# 9_EXTRAS.net
KiCad netlist of a schematic drawn in Altium Designer
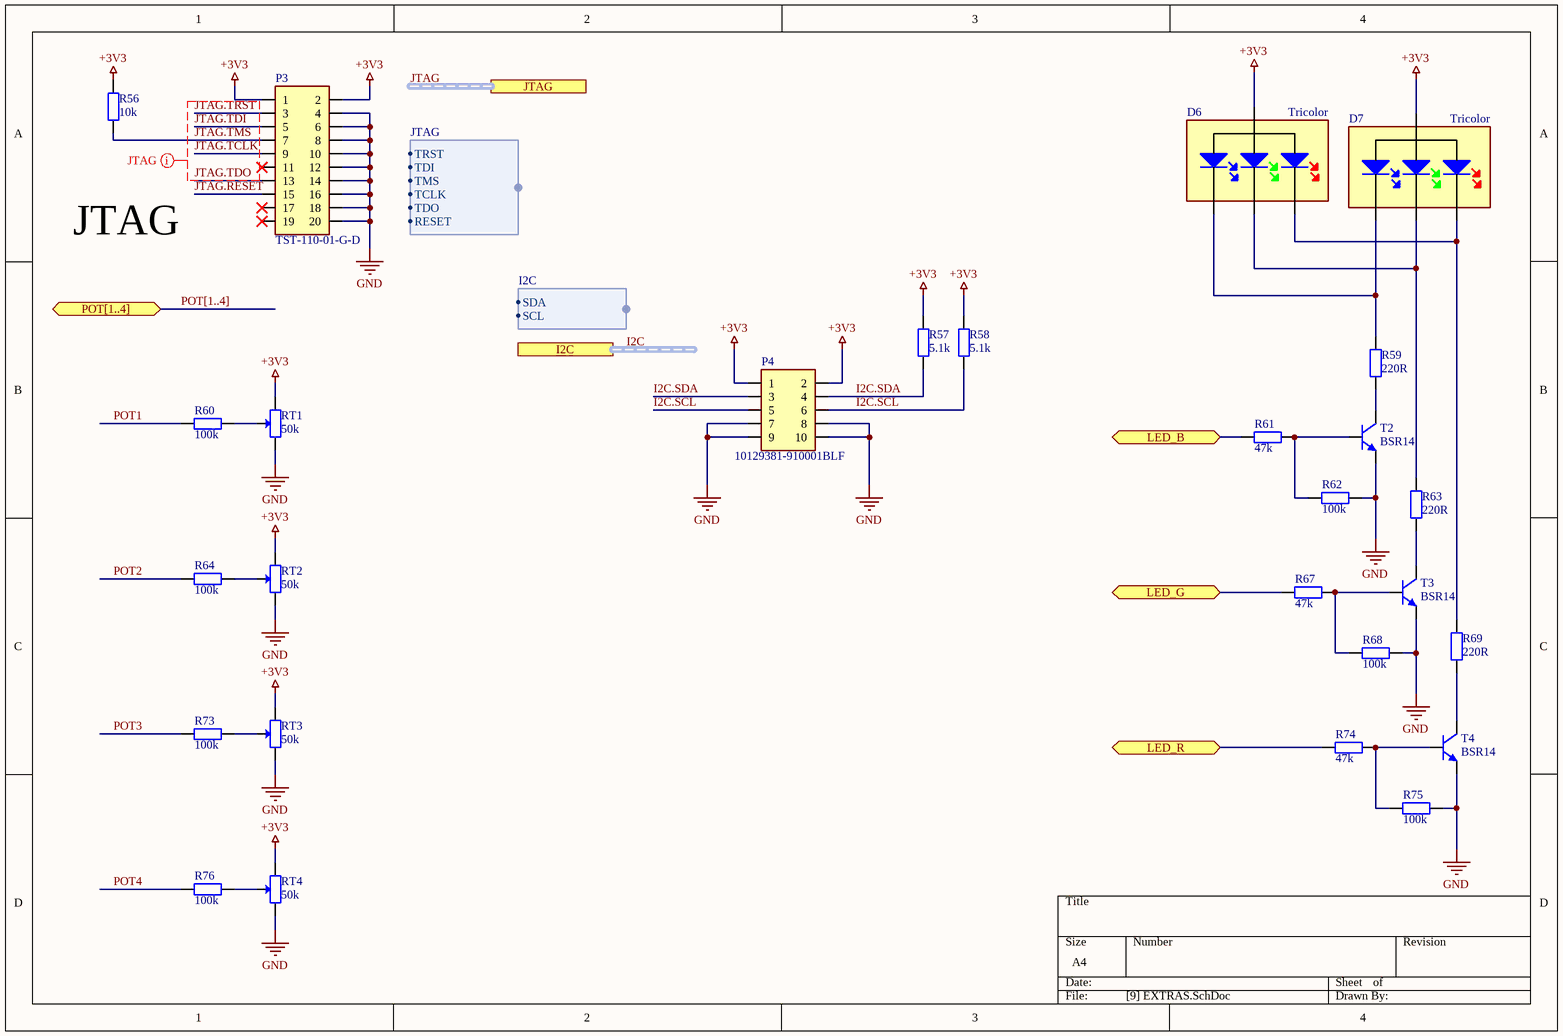
[diagram p0: [9] EXTRAS.SchDoc]

(export (version "E")
  (design (tool "Eeschema 10.0.6"))
  (components
    (comp (ref "D6")
      (value "Tricolor")
      (footprint "STguitar:LED RGB THT")
      (description "Standard LEDs - Through Hole 5MM RGB LED")
      (fields
        (field (name "MANUFACTURER PART NUMBER") "WP154A4SEJ3VBDZGC/CA")
        (field (name "MANUFACTURER") "Kingbright")
      )
      (libsource (lib "STguitar") (part "Diode Standard LEDs - Through Hole 5MM RGB LED"))
    )
    (comp (ref "D7")
      (value "Tricolor")
      (footprint "STguitar:PLCC-4")
      (description "Standard LEDs - SMD 2121 PLCC4 tricolor")
      (fields
        (field (name "MANUFACTURER PART NUMBER") "ASMB-LTB2-0A333")
        (field (name "MANUFACTURER") "Broadcom / Avago")
      )
      (libsource (lib "STguitar") (part "Diode Standard LEDs - SMD 2121 PLCC4 tricolor"))
    )
    (comp (ref "P3")
      (value "TST-110-01-G-D")
      (footprint "STguitar:20 pin 2.54mm male THT JTAG")
      (description "Headers & Wire Housings .100\" Shrouded Terminal Strip, Cable Mate")
      (fields (field (name "MANUFACTURER") "Samtec"))
      (libsource (lib "STguitar") (part "Mechanical Headers & Wire Housings .100{dblquote} Shrouded Terminal Strip, Cable Mate TST-110-01-G-D"))
    )
    (comp (ref "P4")
      (value "10129381-910001BLF")
      (footprint "STguitar:10 PIN THT")
      (description "Headers & Wire Housings ECONOSTIK HEADER DR VT TH 2X5")
      (fields (field (name "MANUFACTURER") "Amphenol FCI"))
      (libsource (lib "STguitar") (part "Mechanical Headers & Wire Housings ECONOSTIK HEADER DR VT TH 2X5"))
    )
    (comp (ref "R56")
      (value "10k")
      (footprint "STguitar:Resistor 0603")
      (description "Thin Film Resistors - SMD 10K ohm 1% 1/10W")
      (fields
        (field (name "MANUFACTURER PART NUMBER") "RT0603FRE0710KL")
        (field (name "MANUFACTURER") "Yageo")
      )
      (libsource (lib "STguitar") (part "Resistor 10k 1% 0603 RT0603FRE0710KL"))
    )
    (comp (ref "R57")
      (value "5.1k")
      (footprint "STguitar:Resistor 0603")
      (description "Thin Film Resistors - SMD 1/10W 5.1K ohm 1% 50ppm")
      (fields
        (field (name "MANUFACTURER PART NUMBER") "RT0603FRE075K1L")
        (field (name "MANUFACTURER") "Yageo")
      )
      (libsource (lib "STguitar") (part "Resistor 5.1k 1% 0603 RT0603FRE075K1L"))
    )
    (comp (ref "R58")
      (value "5.1k")
      (footprint "STguitar:Resistor 0603")
      (description "Thin Film Resistors - SMD 1/10W 5.1K ohm 1% 50ppm")
      (fields
        (field (name "MANUFACTURER PART NUMBER") "RT0603FRE075K1L")
        (field (name "MANUFACTURER") "Yageo")
      )
      (libsource (lib "STguitar") (part "Resistor 5.1k 1% 0603 RT0603FRE075K1L"))
    )
    (comp (ref "R59")
      (value "220R")
      (footprint "STguitar:Resistor 0603")
      (description "Thin Film Resistors - SMD 1/10W 220 ohm 1% 50ppm")
      (fields
        (field (name "MANUFACTURER PART NUMBER") "RT0603FRE07220RL")
        (field (name "MANUFACTURER") "Yageo")
      )
      (libsource (lib "STguitar") (part "Resistor 220R 1% 0603 RT0603FRE07220RL"))
    )
    (comp (ref "R60")
      (value "100k")
      (footprint "STguitar:Resistor 0603")
      (description "Thin Film Resistors - SMD 100K ohm 1% 1/10W")
      (fields
        (field (name "MANUFACTURER PART NUMBER") "RT0603FRE07100KL")
        (field (name "MANUFACTURER") "Yageo")
      )
      (libsource (lib "STguitar") (part "Resistor 100k 1% 0603 RT0603FRE07100KL"))
    )
    (comp (ref "R61")
      (value "47k")
      (footprint "STguitar:Resistor 0603")
      (description "Thin Film Resistors - SMD 1/10W 47K ohm 1% 50ppm")
      (fields
        (field (name "MANUFACTURER PART NUMBER") "RT0603FRE0747KL")
        (field (name "MANUFACTURER") "Yageo")
      )
      (libsource (lib "STguitar") (part "Resistor 47k 1% 0603 RT0603FRE0747KL"))
    )
    (comp (ref "R62")
      (value "100k")
      (footprint "STguitar:Resistor 0603")
      (description "Thin Film Resistors - SMD 100K ohm 1% 1/10W")
      (fields
        (field (name "MANUFACTURER PART NUMBER") "RT0603FRE07100KL")
        (field (name "MANUFACTURER") "Yageo")
      )
      (libsource (lib "STguitar") (part "Resistor 100k 1% 0603 RT0603FRE07100KL"))
    )
    (comp (ref "R63")
      (value "220R")
      (footprint "STguitar:Resistor 0603")
      (description "Thin Film Resistors - SMD 1/10W 220 ohm 1% 50ppm")
      (fields
        (field (name "MANUFACTURER PART NUMBER") "RT0603FRE07220RL")
        (field (name "MANUFACTURER") "Yageo")
      )
      (libsource (lib "STguitar") (part "Resistor 220R 1% 0603 RT0603FRE07220RL"))
    )
    (comp (ref "R64")
      (value "100k")
      (footprint "STguitar:Resistor 0603")
      (description "Thin Film Resistors - SMD 100K ohm 1% 1/10W")
      (fields
        (field (name "MANUFACTURER PART NUMBER") "RT0603FRE07100KL")
        (field (name "MANUFACTURER") "Yageo")
      )
      (libsource (lib "STguitar") (part "Resistor 100k 1% 0603 RT0603FRE07100KL"))
    )
    (comp (ref "R67")
      (value "47k")
      (footprint "STguitar:Resistor 0603")
      (description "Thin Film Resistors - SMD 1/10W 47K ohm 1% 50ppm")
      (fields
        (field (name "MANUFACTURER PART NUMBER") "RT0603FRE0747KL")
        (field (name "MANUFACTURER") "Yageo")
      )
      (libsource (lib "STguitar") (part "Resistor 47k 1% 0603 RT0603FRE0747KL"))
    )
    (comp (ref "R68")
      (value "100k")
      (footprint "STguitar:Resistor 0603")
      (description "Thin Film Resistors - SMD 100K ohm 1% 1/10W")
      (fields
        (field (name "MANUFACTURER PART NUMBER") "RT0603FRE07100KL")
        (field (name "MANUFACTURER") "Yageo")
      )
      (libsource (lib "STguitar") (part "Resistor 100k 1% 0603 RT0603FRE07100KL"))
    )
    (comp (ref "R69")
      (value "220R")
      (footprint "STguitar:Resistor 0603")
      (description "Thin Film Resistors - SMD 1/10W 220 ohm 1% 50ppm")
      (fields
        (field (name "MANUFACTURER PART NUMBER") "RT0603FRE07220RL")
        (field (name "MANUFACTURER") "Yageo")
      )
      (libsource (lib "STguitar") (part "Resistor 220R 1% 0603 RT0603FRE07220RL"))
    )
    (comp (ref "R73")
      (value "100k")
      (footprint "STguitar:Resistor 0603")
      (description "Thin Film Resistors - SMD 100K ohm 1% 1/10W")
      (fields
        (field (name "MANUFACTURER PART NUMBER") "RT0603FRE07100KL")
        (field (name "MANUFACTURER") "Yageo")
      )
      (libsource (lib "STguitar") (part "Resistor 100k 1% 0603 RT0603FRE07100KL"))
    )
    (comp (ref "R74")
      (value "47k")
      (footprint "STguitar:Resistor 0603")
      (description "Thin Film Resistors - SMD 1/10W 47K ohm 1% 50ppm")
      (fields
        (field (name "MANUFACTURER PART NUMBER") "RT0603FRE0747KL")
        (field (name "MANUFACTURER") "Yageo")
      )
      (libsource (lib "STguitar") (part "Resistor 47k 1% 0603 RT0603FRE0747KL"))
    )
    (comp (ref "R75")
      (value "100k")
      (footprint "STguitar:Resistor 0603")
      (description "Thin Film Resistors - SMD 100K ohm 1% 1/10W")
      (fields
        (field (name "MANUFACTURER PART NUMBER") "RT0603FRE07100KL")
        (field (name "MANUFACTURER") "Yageo")
      )
      (libsource (lib "STguitar") (part "Resistor 100k 1% 0603 RT0603FRE07100KL"))
    )
    (comp (ref "R76")
      (value "100k")
      (footprint "STguitar:Resistor 0603")
      (description "Thin Film Resistors - SMD 100K ohm 1% 1/10W")
      (fields
        (field (name "MANUFACTURER PART NUMBER") "RT0603FRE07100KL")
        (field (name "MANUFACTURER") "Yageo")
      )
      (libsource (lib "STguitar") (part "Resistor 100k 1% 0603 RT0603FRE07100KL"))
    )
    (comp (ref "RT1")
      (value "50k")
      (footprint "STguitar:PTV9")
      (description "PANEL CONTROL - 9MM-ST-CA 50 kohms 15 mm")
      (fields
        (field (name "MANUFACTURER PART NUMBER") "PTV09A-4015U-B503")
        (field (name "MANUFACTURER") "Bourns")
      )
      (libsource (lib "STguitar") (part "Potentiometer PANEL CONTROL - 9MM-ST-CA 50 kohms 15 mm"))
    )
    (comp (ref "RT2")
      (value "50k")
      (footprint "STguitar:PTV9")
      (description "PANEL CONTROL - 9MM-ST-CA 50 kohms 15 mm")
      (fields
        (field (name "MANUFACTURER PART NUMBER") "PTV09A-4015U-B503")
        (field (name "MANUFACTURER") "Bourns")
      )
      (libsource (lib "STguitar") (part "Potentiometer PANEL CONTROL - 9MM-ST-CA 50 kohms 15 mm"))
    )
    (comp (ref "RT3")
      (value "50k")
      (footprint "STguitar:PTV9")
      (description "PANEL CONTROL - 9MM-ST-CA 50 kohms 15 mm")
      (fields
        (field (name "MANUFACTURER PART NUMBER") "PTV09A-4015U-B503")
        (field (name "MANUFACTURER") "Bourns")
      )
      (libsource (lib "STguitar") (part "Potentiometer PANEL CONTROL - 9MM-ST-CA 50 kohms 15 mm"))
    )
    (comp (ref "RT4")
      (value "50k")
      (footprint "STguitar:PTV9")
      (description "PANEL CONTROL - 9MM-ST-CA 50 kohms 15 mm")
      (fields
        (field (name "MANUFACTURER PART NUMBER") "PTV09A-4015U-B503")
        (field (name "MANUFACTURER") "Bourns")
      )
      (libsource (lib "STguitar") (part "Potentiometer PANEL CONTROL - 9MM-ST-CA 50 kohms 15 mm"))
    )
    (comp (ref "T2")
      (value "BSR14")
      (footprint "STguitar:SOT23-3")
      (description "Bipolar Transistors - BJT NPN Transistor General Purpose")
      (fields (field (name "MANUFACTURER") "ON Semiconductor / Fairchild"))
      (libsource (lib "STguitar") (part "Transistor Bipolar Transistor - BJT NPN Transistor General Purpose"))
    )
    (comp (ref "T3")
      (value "BSR14")
      (footprint "STguitar:SOT23-3")
      (description "Bipolar Transistors - BJT NPN Transistor General Purpose")
      (fields (field (name "MANUFACTURER") "ON Semiconductor / Fairchild"))
      (libsource (lib "STguitar") (part "Transistor Bipolar Transistor - BJT NPN Transistor General Purpose"))
    )
    (comp (ref "T4")
      (value "BSR14")
      (footprint "STguitar:SOT23-3")
      (description "Bipolar Transistors - BJT NPN Transistor General Purpose")
      (fields (field (name "MANUFACTURER") "ON Semiconductor / Fairchild"))
      (libsource (lib "STguitar") (part "Transistor Bipolar Transistor - BJT NPN Transistor General Purpose"))
    )
  )
  (nets
    (net (code "3") (name "+3V3") (class "Default")
      (node (ref "D6") (pin "2") (pinfunction "2_2") (pintype "passive"))
      (node (ref "D7") (pin "1") (pinfunction "1_1") (pintype "passive"))
      (node (ref "P3") (pin "1") (pinfunction "1_1") (pintype "passive"))
      (node (ref "P3") (pin "2") (pinfunction "2_2") (pintype "passive"))
      (node (ref "P4") (pin "1") (pinfunction "1_1") (pintype "passive"))
      (node (ref "P4") (pin "2") (pinfunction "2_2") (pintype "passive"))
      (node (ref "R56") (pin "2") (pinfunction "2_2") (pintype "passive"))
      (node (ref "R57") (pin "2") (pinfunction "2_2") (pintype "passive"))
      (node (ref "R58") (pin "2") (pinfunction "2_2") (pintype "passive"))
      (node (ref "RT1") (pin "3") (pinfunction "3_3") (pintype "passive"))
      (node (ref "RT2") (pin "3") (pinfunction "3_3") (pintype "passive"))
      (node (ref "RT3") (pin "3") (pinfunction "3_3") (pintype "passive"))
      (node (ref "RT4") (pin "3") (pinfunction "3_3") (pintype "passive"))
    )
    (net (code "4") (name "/I2C.SCL") (class "Default")
      (node (ref "P4") (pin "5") (pinfunction "5_5") (pintype "passive"))
      (node (ref "P4") (pin "6") (pinfunction "6_6") (pintype "passive"))
      (node (ref "R58") (pin "1") (pinfunction "1_1") (pintype "passive"))
    )
    (net (code "5") (name "/I2C.SDA") (class "Default")
      (node (ref "P4") (pin "3") (pinfunction "3_3") (pintype "passive"))
      (node (ref "P4") (pin "4") (pinfunction "4_4") (pintype "passive"))
      (node (ref "R57") (pin "1") (pinfunction "1_1") (pintype "passive"))
    )
    (net (code "6") (name "/JTAG.RESET") (class "Default")
      (node (ref "P3") (pin "15") (pinfunction "15_15") (pintype "passive"))
    )
    (net (code "7") (name "/JTAG.TCLK") (class "Default")
      (node (ref "P3") (pin "9") (pinfunction "9_9") (pintype "passive"))
    )
    (net (code "8") (name "/JTAG.TDI") (class "Default")
      (node (ref "P3") (pin "5") (pinfunction "5_5") (pintype "passive"))
    )
    (net (code "9") (name "/JTAG.TDO") (class "Default")
      (node (ref "P3") (pin "13") (pinfunction "13_13") (pintype "passive"))
    )
    (net (code "10") (name "/JTAG.TMS") (class "Default")
      (node (ref "P3") (pin "7") (pinfunction "7_7") (pintype "passive"))
      (node (ref "R56") (pin "1") (pinfunction "1_1") (pintype "passive"))
    )
    (net (code "11") (name "/JTAG.TRST") (class "Default")
      (node (ref "P3") (pin "3") (pinfunction "3_3") (pintype "passive"))
    )
    (net (code "12") (name "/LED_B") (class "Default")
      (node (ref "R61") (pin "2") (pinfunction "2_2") (pintype "passive"))
    )
    (net (code "13") (name "/LED_G") (class "Default")
      (node (ref "R67") (pin "2") (pinfunction "2_2") (pintype "passive"))
    )
    (net (code "14") (name "/LED_R") (class "Default")
      (node (ref "R74") (pin "2") (pinfunction "2_2") (pintype "passive"))
    )
    (net (code "15") (name "/POT1") (class "Default")
      (node (ref "R60") (pin "1") (pinfunction "1_1") (pintype "passive"))
    )
    (net (code "16") (name "/POT2") (class "Default")
      (node (ref "R64") (pin "1") (pinfunction "1_1") (pintype "passive"))
    )
    (net (code "17") (name "/POT3") (class "Default")
      (node (ref "R73") (pin "1") (pinfunction "1_1") (pintype "passive"))
    )
    (net (code "18") (name "/POT4") (class "Default")
      (node (ref "R76") (pin "1") (pinfunction "1_1") (pintype "passive"))
    )
    (net (code "22") (name "GND") (class "Default")
      (node (ref "P3") (pin "10") (pinfunction "10_10") (pintype "passive"))
      (node (ref "P3") (pin "12") (pinfunction "12_12") (pintype "passive"))
      (node (ref "P3") (pin "14") (pinfunction "14_14") (pintype "passive"))
      (node (ref "P3") (pin "16") (pinfunction "16_16") (pintype "passive"))
      (node (ref "P3") (pin "18") (pinfunction "18_18") (pintype "passive"))
      (node (ref "P3") (pin "20") (pinfunction "20_20") (pintype "passive"))
      (node (ref "P3") (pin "4") (pinfunction "4_4") (pintype "passive"))
      (node (ref "P3") (pin "6") (pinfunction "6_6") (pintype "passive"))
      (node (ref "P3") (pin "8") (pinfunction "8_8") (pintype "passive"))
      (node (ref "P4") (pin "10") (pinfunction "10_10") (pintype "passive"))
      (node (ref "P4") (pin "7") (pinfunction "7_7") (pintype "passive"))
      (node (ref "P4") (pin "8") (pinfunction "8_8") (pintype "passive"))
      (node (ref "P4") (pin "9") (pinfunction "9_9") (pintype "passive"))
      (node (ref "R62") (pin "2") (pinfunction "2_2") (pintype "passive"))
      (node (ref "R68") (pin "2") (pinfunction "2_2") (pintype "passive"))
      (node (ref "R75") (pin "2") (pinfunction "2_2") (pintype "passive"))
      (node (ref "RT1") (pin "1") (pinfunction "1_1") (pintype "passive"))
      (node (ref "RT2") (pin "1") (pinfunction "1_1") (pintype "passive"))
      (node (ref "RT3") (pin "1") (pinfunction "1_1") (pintype "passive"))
      (node (ref "RT4") (pin "1") (pinfunction "1_1") (pintype "passive"))
      (node (ref "T2") (pin "3") (pinfunction "3_3") (pintype "passive"))
      (node (ref "T3") (pin "3") (pinfunction "3_3") (pintype "passive"))
      (node (ref "T4") (pin "3") (pinfunction "3_3") (pintype "passive"))
    )
    (net (code "23") (name "Net-(D6-Pad1)") (class "Default")
      (node (ref "D6") (pin "1") (pinfunction "1_1") (pintype "passive"))
      (node (ref "D7") (pin "2") (pinfunction "2_2") (pintype "passive"))
      (node (ref "R69") (pin "2") (pinfunction "2_2") (pintype "passive"))
    )
    (net (code "24") (name "Net-(D6-Pad3)") (class "Default")
      (node (ref "D6") (pin "3") (pinfunction "3_3") (pintype "passive"))
      (node (ref "D7") (pin "4") (pinfunction "4_4") (pintype "passive"))
      (node (ref "R59") (pin "2") (pinfunction "2_2") (pintype "passive"))
    )
    (net (code "25") (name "Net-(D6-Pad4)") (class "Default")
      (node (ref "D6") (pin "4") (pinfunction "4_4") (pintype "passive"))
      (node (ref "D7") (pin "3") (pinfunction "3_3") (pintype "passive"))
      (node (ref "R63") (pin "2") (pinfunction "2_2") (pintype "passive"))
    )
    (net (code "26") (name "Net-(R59-Pad1)") (class "Default")
      (node (ref "R59") (pin "1") (pinfunction "1_1") (pintype "passive"))
      (node (ref "T2") (pin "2") (pinfunction "2_2") (pintype "passive"))
    )
    (net (code "27") (name "Net-(R60-Pad2)") (class "Default")
      (node (ref "R60") (pin "2") (pinfunction "2_2") (pintype "passive"))
      (node (ref "RT1") (pin "2") (pinfunction "2_2") (pintype "passive"))
    )
    (net (code "28") (name "Net-(R61-Pad1)") (class "Default")
      (node (ref "R61") (pin "1") (pinfunction "1_1") (pintype "passive"))
      (node (ref "R62") (pin "1") (pinfunction "1_1") (pintype "passive"))
      (node (ref "T2") (pin "1") (pinfunction "1_1") (pintype "passive"))
    )
    (net (code "29") (name "Net-(R63-Pad1)") (class "Default")
      (node (ref "R63") (pin "1") (pinfunction "1_1") (pintype "passive"))
      (node (ref "T3") (pin "2") (pinfunction "2_2") (pintype "passive"))
    )
    (net (code "30") (name "Net-(R64-Pad2)") (class "Default")
      (node (ref "R64") (pin "2") (pinfunction "2_2") (pintype "passive"))
      (node (ref "RT2") (pin "2") (pinfunction "2_2") (pintype "passive"))
    )
    (net (code "31") (name "Net-(R67-Pad1)") (class "Default")
      (node (ref "R67") (pin "1") (pinfunction "1_1") (pintype "passive"))
      (node (ref "R68") (pin "1") (pinfunction "1_1") (pintype "passive"))
      (node (ref "T3") (pin "1") (pinfunction "1_1") (pintype "passive"))
    )
    (net (code "32") (name "Net-(R69-Pad1)") (class "Default")
      (node (ref "R69") (pin "1") (pinfunction "1_1") (pintype "passive"))
      (node (ref "T4") (pin "2") (pinfunction "2_2") (pintype "passive"))
    )
    (net (code "33") (name "Net-(R73-Pad2)") (class "Default")
      (node (ref "R73") (pin "2") (pinfunction "2_2") (pintype "passive"))
      (node (ref "RT3") (pin "2") (pinfunction "2_2") (pintype "passive"))
    )
    (net (code "34") (name "Net-(R74-Pad1)") (class "Default")
      (node (ref "R74") (pin "1") (pinfunction "1_1") (pintype "passive"))
      (node (ref "R75") (pin "1") (pinfunction "1_1") (pintype "passive"))
      (node (ref "T4") (pin "1") (pinfunction "1_1") (pintype "passive"))
    )
    (net (code "35") (name "Net-(R76-Pad2)") (class "Default")
      (node (ref "R76") (pin "2") (pinfunction "2_2") (pintype "passive"))
      (node (ref "RT4") (pin "2") (pinfunction "2_2") (pintype "passive"))
    )
    (net (code "36") (name "unconnected-(P3-Pad11)") (class "Default")
      (node (ref "P3") (pin "11") (pinfunction "11_11") (pintype "passive+no_connect"))
    )
    (net (code "37") (name "unconnected-(P3-Pad17)") (class "Default")
      (node (ref "P3") (pin "17") (pinfunction "17_17") (pintype "passive+no_connect"))
    )
    (net (code "38") (name "unconnected-(P3-Pad19)") (class "Default")
      (node (ref "P3") (pin "19") (pinfunction "19_19") (pintype "passive+no_connect"))
    )
  )
)
